# dumbpad.net
KiCad netlist of a schematic drawn in EAGLE
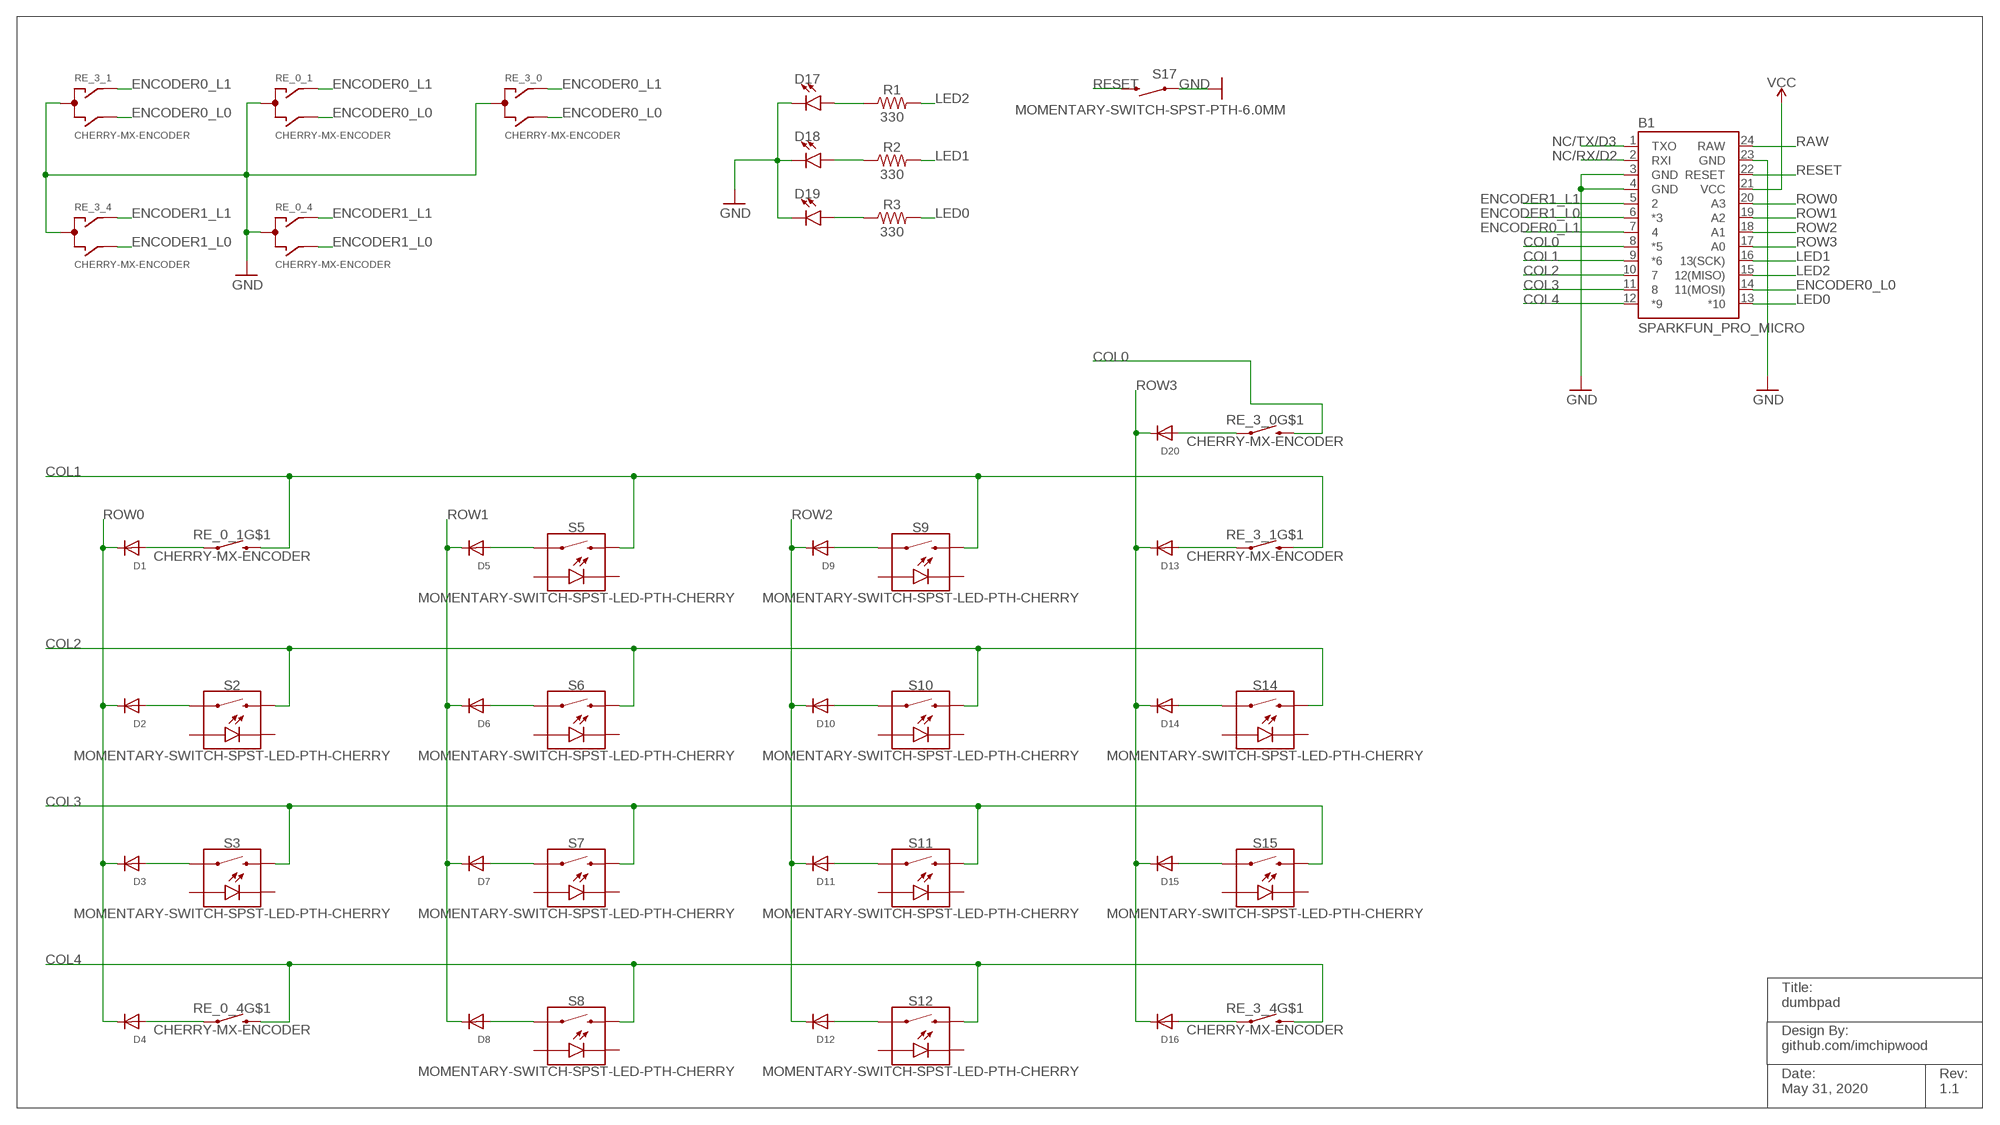
[diagram p0: schematic, sheet 1]

(export (version "E")
  (design (tool "Eeschema 10.0.6"))
  (components
    (comp (ref "B1")
      (value "SPARKFUN_PRO_MICRO")
      (footprint "eagle-import:SPARKFUN_PRO_MICRO")
      (libsource (lib "eagle-import") (part "SPARKFUN_PRO_MICRO"))
    )
    (comp (ref "D1")
      (value "DIODEDO-1N4148")
      (footprint "eagle-import:DO-1N4148")
      (libsource (lib "eagle-import") (part "DIODEDO-1N4148"))
    )
    (comp (ref "D2")
      (value "DIODEDO-1N4148")
      (footprint "eagle-import:DO-1N4148")
      (libsource (lib "eagle-import") (part "DIODEDO-1N4148"))
    )
    (comp (ref "D3")
      (value "DIODEDO-1N4148")
      (footprint "eagle-import:DO-1N4148")
      (libsource (lib "eagle-import") (part "DIODEDO-1N4148"))
    )
    (comp (ref "D4")
      (value "DIODEDO-1N4148")
      (footprint "eagle-import:DO-1N4148")
      (libsource (lib "eagle-import") (part "DIODEDO-1N4148"))
    )
    (comp (ref "D5")
      (value "DIODEDO-1N4148")
      (footprint "eagle-import:DO-1N4148")
      (libsource (lib "eagle-import") (part "DIODEDO-1N4148"))
    )
    (comp (ref "D6")
      (value "DIODEDO-1N4148")
      (footprint "eagle-import:DO-1N4148")
      (libsource (lib "eagle-import") (part "DIODEDO-1N4148"))
    )
    (comp (ref "D7")
      (value "DIODEDO-1N4148")
      (footprint "eagle-import:DO-1N4148")
      (libsource (lib "eagle-import") (part "DIODEDO-1N4148"))
    )
    (comp (ref "D8")
      (value "DIODEDO-1N4148")
      (footprint "eagle-import:DO-1N4148")
      (libsource (lib "eagle-import") (part "DIODEDO-1N4148"))
    )
    (comp (ref "D9")
      (value "DIODEDO-1N4148")
      (footprint "eagle-import:DO-1N4148")
      (libsource (lib "eagle-import") (part "DIODEDO-1N4148"))
    )
    (comp (ref "D10")
      (value "DIODEDO-1N4148")
      (footprint "eagle-import:DO-1N4148")
      (libsource (lib "eagle-import") (part "DIODEDO-1N4148"))
    )
    (comp (ref "D11")
      (value "DIODEDO-1N4148")
      (footprint "eagle-import:DO-1N4148")
      (libsource (lib "eagle-import") (part "DIODEDO-1N4148"))
    )
    (comp (ref "D12")
      (value "DIODEDO-1N4148")
      (footprint "eagle-import:DO-1N4148")
      (libsource (lib "eagle-import") (part "DIODEDO-1N4148"))
    )
    (comp (ref "D13")
      (value "DIODEDO-1N4148")
      (footprint "eagle-import:DO-1N4148")
      (libsource (lib "eagle-import") (part "DIODEDO-1N4148"))
    )
    (comp (ref "D14")
      (value "DIODEDO-1N4148")
      (footprint "eagle-import:DO-1N4148")
      (libsource (lib "eagle-import") (part "DIODEDO-1N4148"))
    )
    (comp (ref "D15")
      (value "DIODEDO-1N4148")
      (footprint "eagle-import:DO-1N4148")
      (libsource (lib "eagle-import") (part "DIODEDO-1N4148"))
    )
    (comp (ref "D16")
      (value "DIODEDO-1N4148")
      (footprint "eagle-import:DO-1N4148")
      (libsource (lib "eagle-import") (part "DIODEDO-1N4148"))
    )
    (comp (ref "D17")
      (value "LED3MM")
      (footprint "eagle-import:LED_3MM")
      (libsource (lib "eagle-import") (part "LED3MM"))
    )
    (comp (ref "D18")
      (value "LED3MM")
      (footprint "eagle-import:LED_3MM")
      (libsource (lib "eagle-import") (part "LED3MM"))
    )
    (comp (ref "D19")
      (value "LED3MM")
      (footprint "eagle-import:LED_3MM")
      (libsource (lib "eagle-import") (part "LED3MM"))
    )
    (comp (ref "D20")
      (value "DIODEDO-1N4148")
      (footprint "eagle-import:DO-1N4148")
      (libsource (lib "eagle-import") (part "DIODEDO-1N4148"))
    )
    (comp (ref "R1")
      (value "330")
      (footprint "eagle-import:AXIAL-0.3")
      (libsource (lib "eagle-import") (part "330OHM-HORIZ-1/10W-5%"))
    )
    (comp (ref "R2")
      (value "330")
      (footprint "eagle-import:AXIAL-0.3")
      (libsource (lib "eagle-import") (part "330OHM-HORIZ-1/10W-5%"))
    )
    (comp (ref "R3")
      (value "330")
      (footprint "eagle-import:AXIAL-0.3")
      (libsource (lib "eagle-import") (part "330OHM-HORIZ-1/10W-5%"))
    )
    (comp (ref "RE_0_1")
      (value "CHERRY-MX-ENCODER")
      (footprint "eagle-import:CHERRY-MX-ENCODER")
      (libsource (lib "eagle-import") (part "CHERRY-MX-ENCODER"))
    )
    (comp (ref "RE_0_4")
      (value "CHERRY-MX-ENCODER")
      (footprint "eagle-import:CHERRY-MX-ENCODER")
      (libsource (lib "eagle-import") (part "CHERRY-MX-ENCODER"))
    )
    (comp (ref "RE_3_0")
      (value "CHERRY-MX-ENCODER")
      (footprint "eagle-import:CHERRY-MX-ENCODER")
      (libsource (lib "eagle-import") (part "CHERRY-MX-ENCODER"))
    )
    (comp (ref "RE_3_1")
      (value "CHERRY-MX-ENCODER")
      (footprint "eagle-import:CHERRY-MX-ENCODER")
      (libsource (lib "eagle-import") (part "CHERRY-MX-ENCODER"))
    )
    (comp (ref "RE_3_4")
      (value "CHERRY-MX-ENCODER")
      (footprint "eagle-import:CHERRY-MX-ENCODER")
      (libsource (lib "eagle-import") (part "CHERRY-MX-ENCODER"))
    )
    (comp (ref "S2")
      (value "MOMENTARY-SWITCH-SPST-LED-PTH-CHERRY")
      (footprint "eagle-import:CHERRY-MX-LED")
      (libsource (lib "eagle-import") (part "MOMENTARY-SWITCH-SPST-LED-PTH-CHERRY"))
    )
    (comp (ref "S3")
      (value "MOMENTARY-SWITCH-SPST-LED-PTH-CHERRY")
      (footprint "eagle-import:CHERRY-MX-LED")
      (libsource (lib "eagle-import") (part "MOMENTARY-SWITCH-SPST-LED-PTH-CHERRY"))
    )
    (comp (ref "S5")
      (value "MOMENTARY-SWITCH-SPST-LED-PTH-CHERRY")
      (footprint "eagle-import:CHERRY-MX-LED")
      (libsource (lib "eagle-import") (part "MOMENTARY-SWITCH-SPST-LED-PTH-CHERRY"))
    )
    (comp (ref "S6")
      (value "MOMENTARY-SWITCH-SPST-LED-PTH-CHERRY")
      (footprint "eagle-import:CHERRY-MX-LED")
      (libsource (lib "eagle-import") (part "MOMENTARY-SWITCH-SPST-LED-PTH-CHERRY"))
    )
    (comp (ref "S7")
      (value "MOMENTARY-SWITCH-SPST-LED-PTH-CHERRY")
      (footprint "eagle-import:CHERRY-MX-LED")
      (libsource (lib "eagle-import") (part "MOMENTARY-SWITCH-SPST-LED-PTH-CHERRY"))
    )
    (comp (ref "S8")
      (value "MOMENTARY-SWITCH-SPST-LED-PTH-CHERRY")
      (footprint "eagle-import:CHERRY-MX-LED")
      (libsource (lib "eagle-import") (part "MOMENTARY-SWITCH-SPST-LED-PTH-CHERRY"))
    )
    (comp (ref "S9")
      (value "MOMENTARY-SWITCH-SPST-LED-PTH-CHERRY")
      (footprint "eagle-import:CHERRY-MX-LED")
      (libsource (lib "eagle-import") (part "MOMENTARY-SWITCH-SPST-LED-PTH-CHERRY"))
    )
    (comp (ref "S10")
      (value "MOMENTARY-SWITCH-SPST-LED-PTH-CHERRY")
      (footprint "eagle-import:CHERRY-MX-LED")
      (libsource (lib "eagle-import") (part "MOMENTARY-SWITCH-SPST-LED-PTH-CHERRY"))
    )
    (comp (ref "S11")
      (value "MOMENTARY-SWITCH-SPST-LED-PTH-CHERRY")
      (footprint "eagle-import:CHERRY-MX-LED")
      (libsource (lib "eagle-import") (part "MOMENTARY-SWITCH-SPST-LED-PTH-CHERRY"))
    )
    (comp (ref "S12")
      (value "MOMENTARY-SWITCH-SPST-LED-PTH-CHERRY")
      (footprint "eagle-import:CHERRY-MX-LED")
      (libsource (lib "eagle-import") (part "MOMENTARY-SWITCH-SPST-LED-PTH-CHERRY"))
    )
    (comp (ref "S14")
      (value "MOMENTARY-SWITCH-SPST-LED-PTH-CHERRY")
      (footprint "eagle-import:CHERRY-MX-LED")
      (libsource (lib "eagle-import") (part "MOMENTARY-SWITCH-SPST-LED-PTH-CHERRY"))
    )
    (comp (ref "S15")
      (value "MOMENTARY-SWITCH-SPST-LED-PTH-CHERRY")
      (footprint "eagle-import:CHERRY-MX-LED")
      (libsource (lib "eagle-import") (part "MOMENTARY-SWITCH-SPST-LED-PTH-CHERRY"))
    )
    (comp (ref "S17")
      (value "MOMENTARY-SWITCH-SPST-PTH-6.0MM")
      (footprint "eagle-import:TACTILE_SWITCH_PTH_6.0MM")
      (libsource (lib "eagle-import") (part "MOMENTARY-SWITCH-SPST-PTH-6.0MM"))
    )
  )
  (nets
    (net (code "1") (name "/COL0") (class "Default")
      (node (ref "B1") (pin "8") (pinfunction "*5_8") (pintype "bidirectional"))
      (node (ref "RE_3_0") (pin "E") (pinfunction "2_E") (pintype "passive"))
      (node (ref "RE_3_0") (pin "S2") (pinfunction "2_S2") (pintype "passive"))
    )
    (net (code "2") (name "/COL1") (class "Default")
      (node (ref "B1") (pin "9") (pinfunction "*6_9") (pintype "bidirectional"))
      (node (ref "RE_0_1") (pin "E") (pinfunction "2_E") (pintype "passive"))
      (node (ref "RE_0_1") (pin "S2") (pinfunction "2_S2") (pintype "passive"))
      (node (ref "RE_3_1") (pin "E") (pinfunction "2_E") (pintype "passive"))
      (node (ref "RE_3_1") (pin "S2") (pinfunction "2_S2") (pintype "passive"))
      (node (ref "S5") (pin "S2") (pinfunction "2_S2") (pintype "passive"))
      (node (ref "S9") (pin "S2") (pinfunction "2_S2") (pintype "passive"))
    )
    (net (code "3") (name "/COL2") (class "Default")
      (node (ref "B1") (pin "10") (pinfunction "7_10") (pintype "bidirectional"))
      (node (ref "S10") (pin "S2") (pinfunction "2_S2") (pintype "passive"))
      (node (ref "S14") (pin "S2") (pinfunction "2_S2") (pintype "passive"))
      (node (ref "S2") (pin "S2") (pinfunction "2_S2") (pintype "passive"))
      (node (ref "S6") (pin "S2") (pinfunction "2_S2") (pintype "passive"))
    )
    (net (code "4") (name "/COL3") (class "Default")
      (node (ref "B1") (pin "11") (pinfunction "8_11") (pintype "bidirectional"))
      (node (ref "S11") (pin "S2") (pinfunction "2_S2") (pintype "passive"))
      (node (ref "S15") (pin "S2") (pinfunction "2_S2") (pintype "passive"))
      (node (ref "S3") (pin "S2") (pinfunction "2_S2") (pintype "passive"))
      (node (ref "S7") (pin "S2") (pinfunction "2_S2") (pintype "passive"))
    )
    (net (code "5") (name "/COL4") (class "Default")
      (node (ref "B1") (pin "12") (pinfunction "*9_12") (pintype "bidirectional"))
      (node (ref "RE_0_4") (pin "E") (pinfunction "2_E") (pintype "passive"))
      (node (ref "RE_0_4") (pin "S2") (pinfunction "2_S2") (pintype "passive"))
      (node (ref "RE_3_4") (pin "E") (pinfunction "2_E") (pintype "passive"))
      (node (ref "RE_3_4") (pin "S2") (pinfunction "2_S2") (pintype "passive"))
      (node (ref "S12") (pin "S2") (pinfunction "2_S2") (pintype "passive"))
      (node (ref "S8") (pin "S2") (pinfunction "2_S2") (pintype "passive"))
    )
    (net (code "6") (name "/ENCODER0_L0") (class "Default")
      (node (ref "B1") (pin "14") (pinfunction "11(MOSI)_14") (pintype "bidirectional"))
      (node (ref "RE_0_1") (pin "B") (pinfunction "B_B") (pintype "passive"))
      (node (ref "RE_3_0") (pin "B") (pinfunction "B_B") (pintype "passive"))
      (node (ref "RE_3_1") (pin "B") (pinfunction "B_B") (pintype "passive"))
    )
    (net (code "7") (name "/ENCODER0_L1") (class "Default")
      (node (ref "B1") (pin "7") (pinfunction "4_7") (pintype "bidirectional"))
      (node (ref "RE_0_1") (pin "A") (pinfunction "A_A") (pintype "passive"))
      (node (ref "RE_3_0") (pin "A") (pinfunction "A_A") (pintype "passive"))
      (node (ref "RE_3_1") (pin "A") (pinfunction "A_A") (pintype "passive"))
    )
    (net (code "8") (name "/ENCODER1_L0") (class "Default")
      (node (ref "B1") (pin "6") (pinfunction "*3_6") (pintype "bidirectional"))
      (node (ref "RE_0_4") (pin "B") (pinfunction "B_B") (pintype "passive"))
      (node (ref "RE_3_4") (pin "B") (pinfunction "B_B") (pintype "passive"))
    )
    (net (code "9") (name "/ENCODER1_L1") (class "Default")
      (node (ref "B1") (pin "5") (pinfunction "2_5") (pintype "bidirectional"))
      (node (ref "RE_0_4") (pin "A") (pinfunction "A_A") (pintype "passive"))
      (node (ref "RE_3_4") (pin "A") (pinfunction "A_A") (pintype "passive"))
    )
    (net (code "10") (name "/LED0") (class "Default")
      (node (ref "B1") (pin "13") (pinfunction "*10_13") (pintype "bidirectional"))
      (node (ref "R3") (pin "P$2") (pinfunction "2_P$2") (pintype "passive"))
    )
    (net (code "11") (name "/LED1") (class "Default")
      (node (ref "B1") (pin "16") (pinfunction "13(SCK)_16") (pintype "bidirectional"))
      (node (ref "R2") (pin "P$2") (pinfunction "2_P$2") (pintype "passive"))
    )
    (net (code "12") (name "/LED2") (class "Default")
      (node (ref "B1") (pin "15") (pinfunction "12(MISO)_15") (pintype "bidirectional"))
      (node (ref "R1") (pin "P$2") (pinfunction "2_P$2") (pintype "passive"))
    )
    (net (code "13") (name "/NC{slash}RX{slash}D2") (class "Default")
      (node (ref "B1") (pin "2") (pinfunction "RXI_2") (pintype "bidirectional"))
    )
    (net (code "14") (name "/NC{slash}TX{slash}D3") (class "Default")
      (node (ref "B1") (pin "1") (pinfunction "TXO_1") (pintype "bidirectional"))
    )
    (net (code "15") (name "/RAW") (class "Default")
      (node (ref "B1") (pin "24") (pinfunction "RAW_24") (pintype "power_in"))
    )
    (net (code "16") (name "/RESET") (class "Default")
      (node (ref "B1") (pin "22") (pinfunction "RESET_22") (pintype "bidirectional"))
      (node (ref "S17") (pin "3") (pinfunction "2_3") (pintype "passive"))
    )
    (net (code "17") (name "/ROW0") (class "Default")
      (node (ref "B1") (pin "20") (pinfunction "A3_20") (pintype "bidirectional"))
      (node (ref "D1") (pin "C") (pinfunction "C_C") (pintype "passive"))
      (node (ref "D2") (pin "C") (pinfunction "C_C") (pintype "passive"))
      (node (ref "D3") (pin "C") (pinfunction "C_C") (pintype "passive"))
      (node (ref "D4") (pin "C") (pinfunction "C_C") (pintype "passive"))
    )
    (net (code "18") (name "/ROW1") (class "Default")
      (node (ref "B1") (pin "19") (pinfunction "A2_19") (pintype "bidirectional"))
      (node (ref "D5") (pin "C") (pinfunction "C_C") (pintype "passive"))
      (node (ref "D6") (pin "C") (pinfunction "C_C") (pintype "passive"))
      (node (ref "D7") (pin "C") (pinfunction "C_C") (pintype "passive"))
      (node (ref "D8") (pin "C") (pinfunction "C_C") (pintype "passive"))
    )
    (net (code "19") (name "/ROW2") (class "Default")
      (node (ref "B1") (pin "18") (pinfunction "A1_18") (pintype "bidirectional"))
      (node (ref "D10") (pin "C") (pinfunction "C_C") (pintype "passive"))
      (node (ref "D11") (pin "C") (pinfunction "C_C") (pintype "passive"))
      (node (ref "D12") (pin "C") (pinfunction "C_C") (pintype "passive"))
      (node (ref "D9") (pin "C") (pinfunction "C_C") (pintype "passive"))
    )
    (net (code "20") (name "/ROW3") (class "Default")
      (node (ref "B1") (pin "17") (pinfunction "A0_17") (pintype "bidirectional"))
      (node (ref "D13") (pin "C") (pinfunction "C_C") (pintype "passive"))
      (node (ref "D14") (pin "C") (pinfunction "C_C") (pintype "passive"))
      (node (ref "D15") (pin "C") (pinfunction "C_C") (pintype "passive"))
      (node (ref "D16") (pin "C") (pinfunction "C_C") (pintype "passive"))
      (node (ref "D20") (pin "C") (pinfunction "C_C") (pintype "passive"))
    )
    (net (code "21") (name "GND") (class "Default")
      (node (ref "B1") (pin "23") (pinfunction "GND_23") (pintype "power_in"))
      (node (ref "B1") (pin "3") (pinfunction "GND_3") (pintype "power_in"))
      (node (ref "B1") (pin "4") (pinfunction "GND_4") (pintype "power_in"))
      (node (ref "D17") (pin "K") (pinfunction "C_K") (pintype "passive"))
      (node (ref "D18") (pin "K") (pinfunction "C_K") (pintype "passive"))
      (node (ref "D19") (pin "K") (pinfunction "C_K") (pintype "passive"))
      (node (ref "RE_0_1") (pin "C") (pinfunction "C_C") (pintype "passive"))
      (node (ref "RE_0_4") (pin "C") (pinfunction "C_C") (pintype "passive"))
      (node (ref "RE_3_0") (pin "C") (pinfunction "C_C") (pintype "passive"))
      (node (ref "RE_3_1") (pin "C") (pinfunction "C_C") (pintype "passive"))
      (node (ref "RE_3_4") (pin "C") (pinfunction "C_C") (pintype "passive"))
      (node (ref "S17") (pin "1") (pinfunction "1_1") (pintype "passive"))
    )
    (net (code "22") (name "Net-(D1-PadA)") (class "Default")
      (node (ref "D1") (pin "A") (pinfunction "A_A") (pintype "passive"))
      (node (ref "RE_0_1") (pin "D") (pinfunction "1_D") (pintype "passive"))
      (node (ref "RE_0_1") (pin "S1") (pinfunction "1_S1") (pintype "passive"))
    )
    (net (code "23") (name "Net-(D4-PadA)") (class "Default")
      (node (ref "D4") (pin "A") (pinfunction "A_A") (pintype "passive"))
      (node (ref "RE_0_4") (pin "D") (pinfunction "1_D") (pintype "passive"))
      (node (ref "RE_0_4") (pin "S1") (pinfunction "1_S1") (pintype "passive"))
    )
    (net (code "24") (name "Net-(D13-PadA)") (class "Default")
      (node (ref "D13") (pin "A") (pinfunction "A_A") (pintype "passive"))
      (node (ref "RE_3_1") (pin "D") (pinfunction "1_D") (pintype "passive"))
      (node (ref "RE_3_1") (pin "S1") (pinfunction "1_S1") (pintype "passive"))
    )
    (net (code "25") (name "Net-(D16-PadA)") (class "Default")
      (node (ref "D16") (pin "A") (pinfunction "A_A") (pintype "passive"))
      (node (ref "RE_3_4") (pin "D") (pinfunction "1_D") (pintype "passive"))
      (node (ref "RE_3_4") (pin "S1") (pinfunction "1_S1") (pintype "passive"))
    )
    (net (code "26") (name "Net-(D20-PadA)") (class "Default")
      (node (ref "D20") (pin "A") (pinfunction "A_A") (pintype "passive"))
      (node (ref "RE_3_0") (pin "D") (pinfunction "1_D") (pintype "passive"))
      (node (ref "RE_3_0") (pin "S1") (pinfunction "1_S1") (pintype "passive"))
    )
    (net (code "27") (name "Net-(R1-1)") (class "Default")
      (node (ref "D17") (pin "A") (pinfunction "A_A") (pintype "passive"))
      (node (ref "R1") (pin "P$1") (pinfunction "1_P$1") (pintype "passive"))
    )
    (net (code "28") (name "Net-(R2-1)") (class "Default")
      (node (ref "D18") (pin "A") (pinfunction "A_A") (pintype "passive"))
      (node (ref "R2") (pin "P$1") (pinfunction "1_P$1") (pintype "passive"))
    )
    (net (code "29") (name "Net-(R3-1)") (class "Default")
      (node (ref "D19") (pin "A") (pinfunction "A_A") (pintype "passive"))
      (node (ref "R3") (pin "P$1") (pinfunction "1_P$1") (pintype "passive"))
    )
    (net (code "30") (name "Net-(S2-1)") (class "Default")
      (node (ref "D2") (pin "A") (pinfunction "A_A") (pintype "passive"))
      (node (ref "S2") (pin "S1") (pinfunction "1_S1") (pintype "passive"))
    )
    (net (code "31") (name "Net-(S3-1)") (class "Default")
      (node (ref "D3") (pin "A") (pinfunction "A_A") (pintype "passive"))
      (node (ref "S3") (pin "S1") (pinfunction "1_S1") (pintype "passive"))
    )
    (net (code "32") (name "Net-(S5-1)") (class "Default")
      (node (ref "D5") (pin "A") (pinfunction "A_A") (pintype "passive"))
      (node (ref "S5") (pin "S1") (pinfunction "1_S1") (pintype "passive"))
    )
    (net (code "33") (name "Net-(S6-1)") (class "Default")
      (node (ref "D6") (pin "A") (pinfunction "A_A") (pintype "passive"))
      (node (ref "S6") (pin "S1") (pinfunction "1_S1") (pintype "passive"))
    )
    (net (code "34") (name "Net-(S7-1)") (class "Default")
      (node (ref "D7") (pin "A") (pinfunction "A_A") (pintype "passive"))
      (node (ref "S7") (pin "S1") (pinfunction "1_S1") (pintype "passive"))
    )
    (net (code "35") (name "Net-(S8-1)") (class "Default")
      (node (ref "D8") (pin "A") (pinfunction "A_A") (pintype "passive"))
      (node (ref "S8") (pin "S1") (pinfunction "1_S1") (pintype "passive"))
    )
    (net (code "36") (name "Net-(S9-1)") (class "Default")
      (node (ref "D9") (pin "A") (pinfunction "A_A") (pintype "passive"))
      (node (ref "S9") (pin "S1") (pinfunction "1_S1") (pintype "passive"))
    )
    (net (code "37") (name "Net-(S10-1)") (class "Default")
      (node (ref "D10") (pin "A") (pinfunction "A_A") (pintype "passive"))
      (node (ref "S10") (pin "S1") (pinfunction "1_S1") (pintype "passive"))
    )
    (net (code "38") (name "Net-(S11-1)") (class "Default")
      (node (ref "D11") (pin "A") (pinfunction "A_A") (pintype "passive"))
      (node (ref "S11") (pin "S1") (pinfunction "1_S1") (pintype "passive"))
    )
    (net (code "39") (name "Net-(S12-1)") (class "Default")
      (node (ref "D12") (pin "A") (pinfunction "A_A") (pintype "passive"))
      (node (ref "S12") (pin "S1") (pinfunction "1_S1") (pintype "passive"))
    )
    (net (code "40") (name "Net-(S14-1)") (class "Default")
      (node (ref "D14") (pin "A") (pinfunction "A_A") (pintype "passive"))
      (node (ref "S14") (pin "S1") (pinfunction "1_S1") (pintype "passive"))
    )
    (net (code "41") (name "Net-(S15-1)") (class "Default")
      (node (ref "D15") (pin "A") (pinfunction "A_A") (pintype "passive"))
      (node (ref "S15") (pin "S1") (pinfunction "1_S1") (pintype "passive"))
    )
    (net (code "42") (name "VCC") (class "Default")
      (node (ref "B1") (pin "21") (pinfunction "VCC_21") (pintype "power_in"))
    )
    (net (code "43") (name "unconnected-(S2-C-PadK)") (class "Default")
      (node (ref "S2") (pin "K") (pinfunction "C_K") (pintype "passive"))
    )
    (net (code "44") (name "unconnected-(S2-PadA)") (class "Default")
      (node (ref "S2") (pin "A") (pinfunction "A_A") (pintype "passive"))
    )
    (net (code "45") (name "unconnected-(S3-C-PadK)") (class "Default")
      (node (ref "S3") (pin "K") (pinfunction "C_K") (pintype "passive"))
    )
    (net (code "46") (name "unconnected-(S3-PadA)") (class "Default")
      (node (ref "S3") (pin "A") (pinfunction "A_A") (pintype "passive"))
    )
    (net (code "47") (name "unconnected-(S5-C-PadK)") (class "Default")
      (node (ref "S5") (pin "K") (pinfunction "C_K") (pintype "passive"))
    )
    (net (code "48") (name "unconnected-(S5-PadA)") (class "Default")
      (node (ref "S5") (pin "A") (pinfunction "A_A") (pintype "passive"))
    )
    (net (code "49") (name "unconnected-(S6-C-PadK)") (class "Default")
      (node (ref "S6") (pin "K") (pinfunction "C_K") (pintype "passive"))
    )
    (net (code "50") (name "unconnected-(S6-PadA)") (class "Default")
      (node (ref "S6") (pin "A") (pinfunction "A_A") (pintype "passive"))
    )
    (net (code "51") (name "unconnected-(S7-C-PadK)") (class "Default")
      (node (ref "S7") (pin "K") (pinfunction "C_K") (pintype "passive"))
    )
    (net (code "52") (name "unconnected-(S7-PadA)") (class "Default")
      (node (ref "S7") (pin "A") (pinfunction "A_A") (pintype "passive"))
    )
    (net (code "53") (name "unconnected-(S8-C-PadK)") (class "Default")
      (node (ref "S8") (pin "K") (pinfunction "C_K") (pintype "passive"))
    )
    (net (code "54") (name "unconnected-(S8-PadA)") (class "Default")
      (node (ref "S8") (pin "A") (pinfunction "A_A") (pintype "passive"))
    )
    (net (code "55") (name "unconnected-(S9-C-PadK)") (class "Default")
      (node (ref "S9") (pin "K") (pinfunction "C_K") (pintype "passive"))
    )
    (net (code "56") (name "unconnected-(S9-PadA)") (class "Default")
      (node (ref "S9") (pin "A") (pinfunction "A_A") (pintype "passive"))
    )
    (net (code "57") (name "unconnected-(S10-C-PadK)") (class "Default")
      (node (ref "S10") (pin "K") (pinfunction "C_K") (pintype "passive"))
    )
    (net (code "58") (name "unconnected-(S10-PadA)") (class "Default")
      (node (ref "S10") (pin "A") (pinfunction "A_A") (pintype "passive"))
    )
    (net (code "59") (name "unconnected-(S11-C-PadK)") (class "Default")
      (node (ref "S11") (pin "K") (pinfunction "C_K") (pintype "passive"))
    )
    (net (code "60") (name "unconnected-(S11-PadA)") (class "Default")
      (node (ref "S11") (pin "A") (pinfunction "A_A") (pintype "passive"))
    )
    (net (code "61") (name "unconnected-(S12-C-PadK)") (class "Default")
      (node (ref "S12") (pin "K") (pinfunction "C_K") (pintype "passive"))
    )
    (net (code "62") (name "unconnected-(S12-PadA)") (class "Default")
      (node (ref "S12") (pin "A") (pinfunction "A_A") (pintype "passive"))
    )
    (net (code "63") (name "unconnected-(S14-C-PadK)") (class "Default")
      (node (ref "S14") (pin "K") (pinfunction "C_K") (pintype "passive"))
    )
    (net (code "64") (name "unconnected-(S14-PadA)") (class "Default")
      (node (ref "S14") (pin "A") (pinfunction "A_A") (pintype "passive"))
    )
    (net (code "65") (name "unconnected-(S15-C-PadK)") (class "Default")
      (node (ref "S15") (pin "K") (pinfunction "C_K") (pintype "passive"))
    )
    (net (code "66") (name "unconnected-(S15-PadA)") (class "Default")
      (node (ref "S15") (pin "A") (pinfunction "A_A") (pintype "passive"))
    )
  )
)
